# MiniGen.net
KiCad netlist of a schematic drawn in Altium Designer
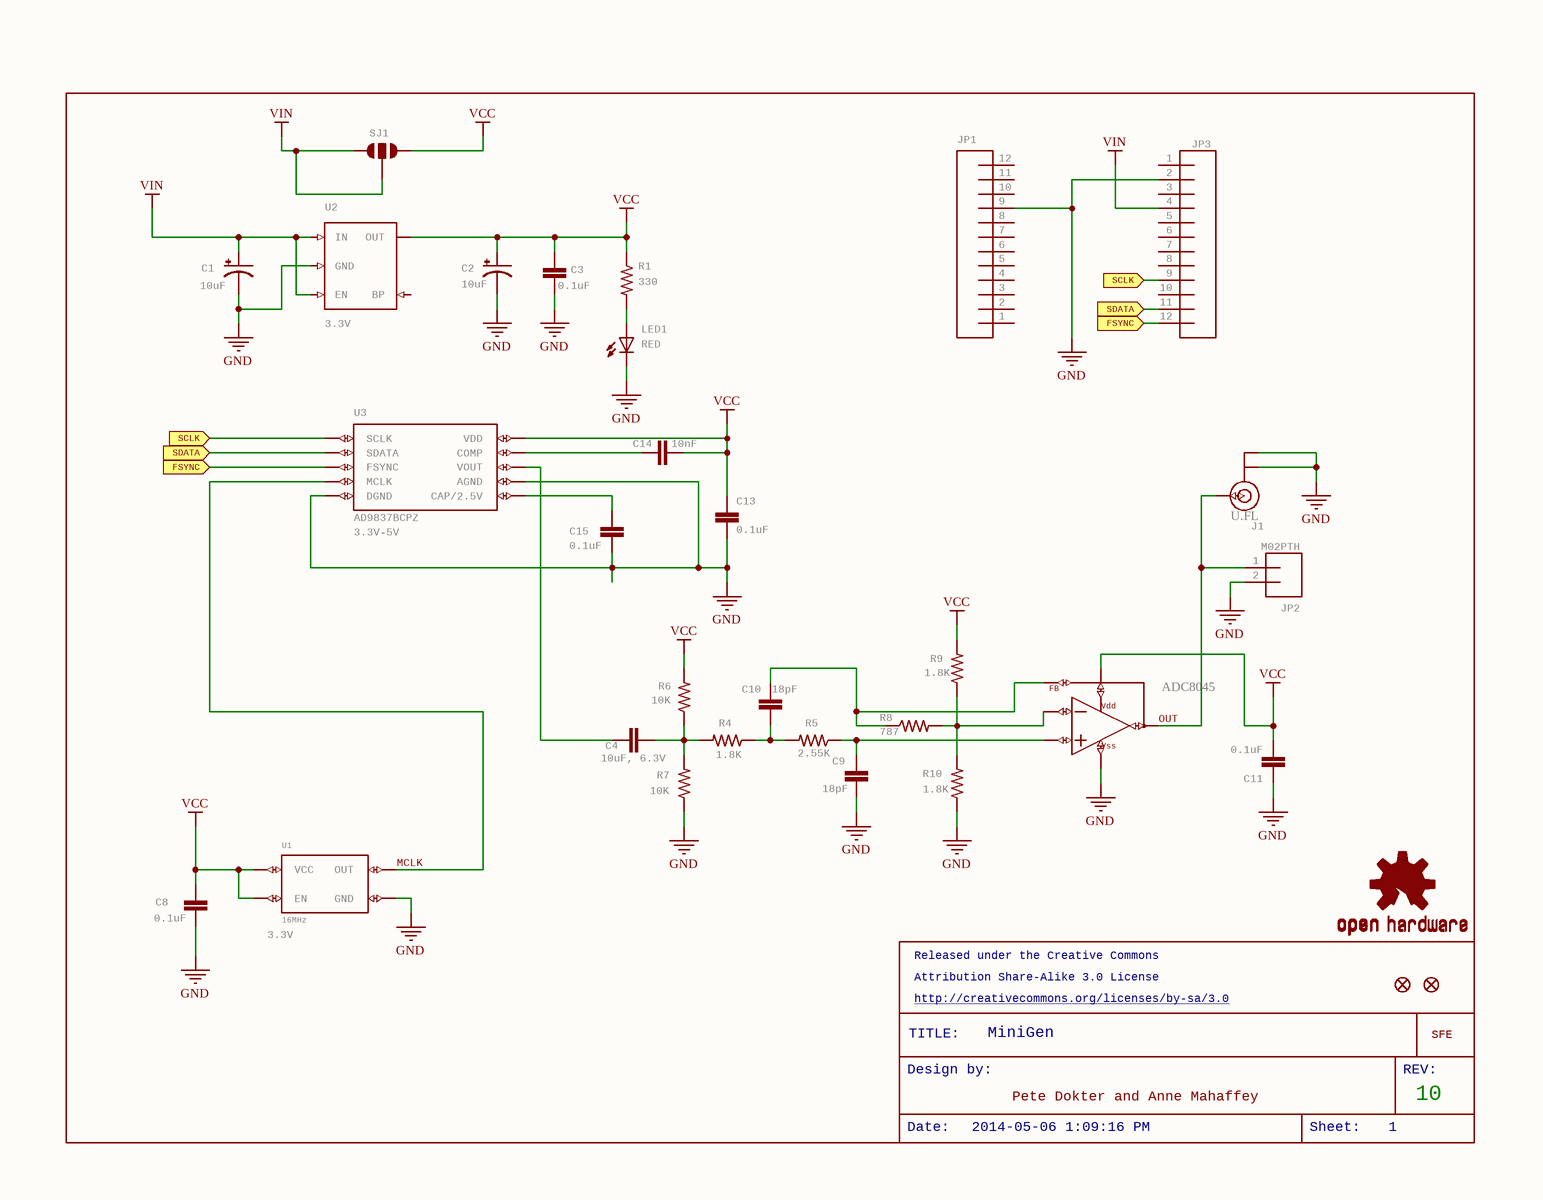
[diagram p0: MiniGen.SchDoc]

(export (version "E")
  (design (tool "Eeschema 10.0.6"))
  (components
    (comp (ref "C1")
      (value "10uF")
      (footprint "EIA3528")
      (description "CAP-08063")
      (libsource (lib "SparkFun-Capacitors") (part "10UF-20V-10%(TANT)"))
    )
    (comp (ref "C2")
      (value "10uF")
      (footprint "EIA3528")
      (description "CAP-08063")
      (libsource (lib "SparkFun-Capacitors") (part "10UF-20V-10%(TANT)"))
    )
    (comp (ref "C3")
      (value "0.1uF")
      (footprint "0603-CAP")
      (description "CAP-00810 Ceramic Standard decoupling cap")
      (libsource (lib "SparkFun-Capacitors") (part "0.1UF-25V(+80/-20%)(0603)"))
    )
    (comp (ref "C4")
      (value "10uF, 6.3V")
      (footprint "0603-CAP")
      (description "CAP-11015")
      (libsource (lib "SparkFun-Capacitors") (part "10UF-6.3V-20%(0603)"))
    )
    (comp (ref "C8")
      (value "0.1uF")
      (footprint "0603-CAP")
      (description "CAP-00810 Ceramic Standard decoupling cap")
      (libsource (lib "SparkFun-Capacitors") (part "0.1UF-25V(+80/-20%)(0603)"))
    )
    (comp (ref "C9")
      (value "18pF")
      (footprint "0603-CAP")
      (description "CAP-08267")
      (libsource (lib "SparkFun-Capacitors") (part "18PF-50V-5%(0603)"))
    )
    (comp (ref "C10")
      (value "18pF")
      (footprint "0603-CAP")
      (description "CAP-08267")
      (libsource (lib "SparkFun-Capacitors") (part "18PF-50V-5%(0603)"))
    )
    (comp (ref "C11")
      (value "0.1uF")
      (footprint "0603-CAP")
      (description "CAP-00810 Ceramic Standard decoupling cap")
      (libsource (lib "") (part "0.1UF-25V(+80/-20%)(0603)_1"))
    )
    (comp (ref "C13")
      (value "0.1uF")
      (footprint "0603-CAP")
      (description "CAP-00810 Ceramic Standard decoupling cap")
      (libsource (lib "SparkFun-Capacitors") (part "0.1UF-25V(+80/-20%)(0603)"))
    )
    (comp (ref "C14")
      (value "10nF")
      (footprint "0603-CAP")
      (description "CAP-00867")
      (libsource (lib "SparkFun-Capacitors") (part "10NF/10000PF-50V-10%(0603)"))
    )
    (comp (ref "C15")
      (value "0.1uF")
      (footprint "0603-CAP")
      (description "CAP-00810 Ceramic Standard decoupling cap")
      (libsource (lib "SparkFun-Capacitors") (part "0.1UF-25V(+80/-20%)(0603)"))
    )
    (comp (ref "FID1")
      (value "FIDUCIAL1X2")
      (footprint "FIDUCIAL-1X2")
      (description "Fiducial Alignment PointsVarious fiducial points for machine vision alignment.")
      (libsource (lib "SparkFun-Aesthetics") (part "FIDUCIAL1X2"))
    )
    (comp (ref "FID2")
      (value "FIDUCIAL1X2")
      (footprint "FIDUCIAL-1X2")
      (description "Fiducial Alignment PointsVarious fiducial points for machine vision alignment.")
      (libsource (lib "SparkFun-Aesthetics") (part "FIDUCIAL1X2"))
    )
    (comp (ref "J1")
      (value "U.FL")
      (footprint "U.FL")
      (description "SMD antenna connector- WRL-09144")
      (libsource (lib "SparkFun-Connectors") (part "U.FL"))
    )
    (comp (ref "JP1")
      (value "M12PTH")
      (footprint "1X12")
      (libsource (lib "SparkFun-Connectors") (part "M12PTH"))
    )
    (comp (ref "JP2")
      (value "M02PTH")
      (footprint "1X02")
      (libsource (lib "SparkFun-Connectors") (part "M02PTH"))
    )
    (comp (ref "JP3")
      (value "M12PTH")
      (footprint "1X12")
      (libsource (lib "SparkFun-Connectors") (part "M12PTH"))
    )
    (comp (ref "JP4")
      (value "LOGO-SFENEW")
      (footprint "SFE-NEW-WEBLOGO")
      (description "Spark Fun Electronics PCB LogoThis is the standard Spark Fun Electronics PCB logo.")
      (fields (field (name "SFE") "SFE"))
      (libsource (lib "SparkFun-Aesthetics") (part "LOGO-SFENEW"))
    )
    (comp (ref "LED1")
      (value "RED")
      (footprint "LED-0603")
      (description "Assorted Red LEDs LilyPad 1206- DIO-09912 1206- DIO-00809 0603- DIO-00819")
      (libsource (lib "SparkFun-LED") (part "LED-RED0603"))
    )
    (comp (ref "R1")
      (value "330")
      (footprint "0603-RES")
      (description "RES-00818")
      (libsource (lib "SparkFun-Resistors") (part "330OHM1/10W1%(0603)"))
    )
    (comp (ref "R4")
      (value "1.8K")
      (footprint "0603-RES")
      (description "RES-09119")
      (libsource (lib "SparkFun-Resistors") (part "1.8KOHM1/10W1%(0603)"))
    )
    (comp (ref "R5")
      (value "2.55K")
      (footprint "0603-RES")
      (description "RES-11227")
      (libsource (lib "SparkFun-Resistors") (part "2.55KOHM-1/10W-1%(0603)"))
    )
    (comp (ref "R6")
      (value "10K")
      (footprint "0603-RES")
      (description "RES-00824")
      (libsource (lib "SparkFun-Resistors") (part "10KOHM1/10W1%(0603)0603"))
    )
    (comp (ref "R7")
      (value "10K")
      (footprint "0603-RES")
      (description "RES-00824")
      (libsource (lib "SparkFun-Resistors") (part "10KOHM1/10W1%(0603)0603"))
    )
    (comp (ref "R8")
      (value "787")
      (footprint "0603-RES")
      (description "787-ohm SMT 1/10W - 1% (0603) RES-11228")
      (libsource (lib "SparkFun-Resistors") (part "787-1%"))
    )
    (comp (ref "R9")
      (value "1.8K")
      (footprint "0603-RES")
      (description "RES-09119")
      (libsource (lib "SparkFun-Resistors") (part "1.8KOHM1/10W1%(0603)"))
    )
    (comp (ref "R10")
      (value "1.8K")
      (footprint "0603-RES")
      (description "RES-09119")
      (libsource (lib "SparkFun-Resistors") (part "1.8KOHM1/10W1%(0603)"))
    )
    (comp (ref "SJ1")
      (value "SOLDERJUMPER_2WAYT")
      (footprint "SJ_2")
      (description "Solder Jumper2 way solder jumper")
      (libsource (lib "SparkFun-Passives") (part "SOLDERJUMPER_2WAYT"))
    )
    (comp (ref "U$2")
      (value "OSHW-LOGOS")
      (footprint "OSHW-LOGO-S")
      (libsource (lib "SparkFun-Aesthetics") (part "OSHW-LOGOS"))
    )
    (comp (ref "U1")
      (value "16MHz")
      (footprint "CRYSTAL-SMD-7X5")
      (description "Generic 5x3 and 7x5 oscillators")
      (fields (field (name "LIBRARYNAME") "SparkFun-FreqCtrl"))
      (libsource (lib "SparkFun-FreqCtrl") (part "OSCILLATORXTAL-11225"))
    )
    (comp (ref "U2")
      (value "3.3V")
      (footprint "SOT23-5")
      (description "MIC5205 150mA vreg 3.3V - VREG-00822 5V - VREG-00823")
      (libsource (lib "SparkFun-PowerIC") (part "MIC52053.3V"))
    )
    (comp (ref "U3")
      (value "AD9837BCPZ")
      (footprint "AD9837")
      (description "Programmable waveform generator, sine, triangular, and square wave outputs.")
      (libsource (lib "SparkFun-AnalogIC") (part "AD9837"))
    )
    (comp (ref "U4")
      (value "ADC8045")
      (footprint "SO08")
      (description "Unity-gain stable feedback amplifier. Low noise, low distortion, 1GHz BW.")
      (fields (field (name "VSS") "Vss") (field (name "VDD") "Vdd") (field (name "FB") "FB"))
      (libsource (lib "SparkFun-AnalogIC") (part "ADC8045"))
    )
  )
  (nets
    (net (code "1") (name "/FSYNC") (class "Default")
      (node (ref "JP3") (pin "12") (pinfunction "12_12") (pintype "passive"))
      (node (ref "U3") (pin "P$8") (pinfunction "FSYNC_P$8") (pintype "bidirectional"))
    )
    (net (code "2") (name "/MCLK") (class "Default")
      (node (ref "U1") (pin "P$3") (pinfunction "OUT_P$3") (pintype "bidirectional"))
      (node (ref "U3") (pin "P$5") (pinfunction "MCLK_P$5") (pintype "bidirectional"))
    )
    (net (code "3") (name "/OUT") (class "Default")
      (node (ref "J1") (pin "P$3") (pinfunction "SIGNAL_P$3") (pintype "bidirectional"))
      (node (ref "JP2") (pin "1") (pinfunction "1_1") (pintype "passive"))
      (node (ref "U4") (pin "6") (pinfunction "OUT_6") (pintype "bidirectional"))
    )
    (net (code "4") (name "/SCLK") (class "Default")
      (node (ref "JP3") (pin "9") (pinfunction "9_9") (pintype "passive"))
      (node (ref "U3") (pin "P$7") (pinfunction "SCLK_P$7") (pintype "bidirectional"))
    )
    (net (code "5") (name "/SDATA") (class "Default")
      (node (ref "JP3") (pin "11") (pinfunction "11_11") (pintype "passive"))
      (node (ref "U3") (pin "P$6") (pinfunction "SDATA_P$6") (pintype "bidirectional"))
    )
    (net (code "6") (name "GND") (class "Default")
      (node (ref "C1") (pin "C") (pinfunction "-_C") (pintype "passive"))
      (node (ref "C11") (pin "1") (pinfunction "1_1") (pintype "passive"))
      (node (ref "C13") (pin "2") (pinfunction "2_2") (pintype "passive"))
      (node (ref "C15") (pin "2") (pinfunction "2_2") (pintype "passive"))
      (node (ref "C2") (pin "C") (pinfunction "-_C") (pintype "passive"))
      (node (ref "C3") (pin "2") (pinfunction "2_2") (pintype "passive"))
      (node (ref "C8") (pin "2") (pinfunction "2_2") (pintype "passive"))
      (node (ref "C9") (pin "1") (pinfunction "1_1") (pintype "passive"))
      (node (ref "J1") (pin "P$1") (pinfunction "GND_P$1") (pintype "bidirectional"))
      (node (ref "J1") (pin "P$2") (pinfunction "GND_P$2") (pintype "bidirectional"))
      (node (ref "JP1") (pin "9") (pinfunction "9_9") (pintype "passive"))
      (node (ref "JP2") (pin "2") (pinfunction "2_2") (pintype "passive"))
      (node (ref "JP3") (pin "2") (pinfunction "2_2") (pintype "passive"))
      (node (ref "LED1") (pin "C") (pinfunction "C_C") (pintype "passive"))
      (node (ref "R10") (pin "1") (pinfunction "1_1") (pintype "passive"))
      (node (ref "R7") (pin "1") (pinfunction "1_1") (pintype "passive"))
      (node (ref "U1") (pin "P$2") (pinfunction "GND_P$2") (pintype "bidirectional"))
      (node (ref "U2") (pin "2") (pinfunction "GND_2") (pintype "input"))
      (node (ref "U3") (pin "P$0_P$4") (pinfunction "DGND_P$0_P$4") (pintype "bidirectional"))
      (node (ref "U3") (pin "P$9") (pinfunction "AGND_P$9") (pintype "bidirectional"))
      (node (ref "U4") (pin "4") (pinfunction "VSS_4") (pintype "bidirectional"))
    )
    (net (code "7") (name "Net-(C4-Pad2)") (class "Default")
      (node (ref "C4") (pin "2") (pinfunction "2_2") (pintype "passive"))
      (node (ref "R4") (pin "2") (pinfunction "2_2") (pintype "passive"))
      (node (ref "R6") (pin "1") (pinfunction "1_1") (pintype "passive"))
      (node (ref "R7") (pin "2") (pinfunction "2_2") (pintype "passive"))
    )
    (net (code "8") (name "Net-(C10-Pad1)") (class "Default")
      (node (ref "C10") (pin "1") (pinfunction "1_1") (pintype "passive"))
      (node (ref "R4") (pin "1") (pinfunction "1_1") (pintype "passive"))
      (node (ref "R5") (pin "2") (pinfunction "2_2") (pintype "passive"))
    )
    (net (code "9") (name "Net-(LED1-PadA)") (class "Default")
      (node (ref "LED1") (pin "A") (pinfunction "A_A") (pintype "passive"))
      (node (ref "R1") (pin "2") (pinfunction "2_2") (pintype "passive"))
    )
    (net (code "10") (name "Net-(U3-CAP{slash}2.5V)") (class "Default")
      (node (ref "C15") (pin "1") (pinfunction "1_1") (pintype "passive"))
      (node (ref "U3") (pin "P$3") (pinfunction "CAP/2.5V_P$3") (pintype "bidirectional"))
    )
    (net (code "11") (name "Net-(U3-COMP)") (class "Default")
      (node (ref "C14") (pin "1") (pinfunction "1_1") (pintype "passive"))
      (node (ref "U3") (pin "P$1") (pinfunction "COMP_P$1") (pintype "bidirectional"))
    )
    (net (code "12") (name "Net-(U3-VOUT)") (class "Default")
      (node (ref "C4") (pin "1") (pinfunction "1_1") (pintype "passive"))
      (node (ref "U3") (pin "P$10") (pinfunction "VOUT_P$10") (pintype "bidirectional"))
    )
    (net (code "13") (name "Net-(U4-FB)") (class "Default")
      (node (ref "C10") (pin "2") (pinfunction "2_2") (pintype "passive"))
      (node (ref "R8") (pin "1") (pinfunction "1_1") (pintype "passive"))
      (node (ref "U4") (pin "1") (pinfunction "FB_1") (pintype "bidirectional"))
    )
    (net (code "14") (name "Net-(U4-IN+)") (class "Default")
      (node (ref "C9") (pin "2") (pinfunction "2_2") (pintype "passive"))
      (node (ref "R5") (pin "1") (pinfunction "1_1") (pintype "passive"))
      (node (ref "U4") (pin "3") (pinfunction "IN+_3") (pintype "bidirectional"))
    )
    (net (code "15") (name "Net-(U4-IN-)") (class "Default")
      (node (ref "R10") (pin "2") (pinfunction "2_2") (pintype "passive"))
      (node (ref "R8") (pin "2") (pinfunction "2_2") (pintype "passive"))
      (node (ref "R9") (pin "1") (pinfunction "1_1") (pintype "passive"))
      (node (ref "U4") (pin "2") (pinfunction "IN-_2") (pintype "bidirectional"))
    )
    (net (code "16") (name "VCC") (class "Default")
      (node (ref "C11") (pin "2") (pinfunction "2_2") (pintype "passive"))
      (node (ref "C13") (pin "1") (pinfunction "1_1") (pintype "passive"))
      (node (ref "C14") (pin "2") (pinfunction "2_2") (pintype "passive"))
      (node (ref "C2") (pin "A") (pinfunction "+_A") (pintype "passive"))
      (node (ref "C3") (pin "1") (pinfunction "1_1") (pintype "passive"))
      (node (ref "C8") (pin "1") (pinfunction "1_1") (pintype "passive"))
      (node (ref "R1") (pin "1") (pinfunction "1_1") (pintype "passive"))
      (node (ref "R6") (pin "2") (pinfunction "2_2") (pintype "passive"))
      (node (ref "R9") (pin "2") (pinfunction "2_2") (pintype "passive"))
      (node (ref "SJ1") (pin "3") (pinfunction "3_3") (pintype "passive"))
      (node (ref "U1") (pin "P$1") (pinfunction "EN_P$1") (pintype "bidirectional"))
      (node (ref "U1") (pin "P$4") (pinfunction "VCC_P$4") (pintype "bidirectional"))
      (node (ref "U2") (pin "5") (pinfunction "OUT_5") (pintype "passive"))
      (node (ref "U3") (pin "P$2") (pinfunction "VDD_P$2") (pintype "bidirectional"))
      (node (ref "U4") (pin "7") (pinfunction "VDD_7") (pintype "bidirectional"))
    )
    (net (code "17") (name "VIN") (class "Default")
      (node (ref "C1") (pin "A") (pinfunction "+_A") (pintype "passive"))
      (node (ref "JP3") (pin "4") (pinfunction "4_4") (pintype "passive"))
      (node (ref "SJ1") (pin "1") (pinfunction "1_1") (pintype "passive"))
      (node (ref "SJ1") (pin "2") (pinfunction "2_2") (pintype "passive"))
      (node (ref "U2") (pin "1") (pinfunction "IN_1") (pintype "input"))
      (node (ref "U2") (pin "3") (pinfunction "EN_3") (pintype "input"))
    )
    (net (code "18") (name "unconnected-(JP1-Pad1)") (class "Default")
      (node (ref "JP1") (pin "1") (pinfunction "1_1") (pintype "passive"))
    )
    (net (code "19") (name "unconnected-(JP1-Pad2)") (class "Default")
      (node (ref "JP1") (pin "2") (pinfunction "2_2") (pintype "passive"))
    )
    (net (code "20") (name "unconnected-(JP1-Pad3)") (class "Default")
      (node (ref "JP1") (pin "3") (pinfunction "3_3") (pintype "passive"))
    )
    (net (code "21") (name "unconnected-(JP1-Pad4)") (class "Default")
      (node (ref "JP1") (pin "4") (pinfunction "4_4") (pintype "passive"))
    )
    (net (code "22") (name "unconnected-(JP1-Pad5)") (class "Default")
      (node (ref "JP1") (pin "5") (pinfunction "5_5") (pintype "passive"))
    )
    (net (code "23") (name "unconnected-(JP1-Pad6)") (class "Default")
      (node (ref "JP1") (pin "6") (pinfunction "6_6") (pintype "passive"))
    )
    (net (code "24") (name "unconnected-(JP1-Pad7)") (class "Default")
      (node (ref "JP1") (pin "7") (pinfunction "7_7") (pintype "passive"))
    )
    (net (code "25") (name "unconnected-(JP1-Pad8)") (class "Default")
      (node (ref "JP1") (pin "8") (pinfunction "8_8") (pintype "passive"))
    )
    (net (code "26") (name "unconnected-(JP1-Pad10)") (class "Default")
      (node (ref "JP1") (pin "10") (pinfunction "10_10") (pintype "passive"))
    )
    (net (code "27") (name "unconnected-(JP1-Pad11)") (class "Default")
      (node (ref "JP1") (pin "11") (pinfunction "11_11") (pintype "passive"))
    )
    (net (code "28") (name "unconnected-(JP1-Pad12)") (class "Default")
      (node (ref "JP1") (pin "12") (pinfunction "12_12") (pintype "passive"))
    )
    (net (code "29") (name "unconnected-(JP3-Pad1)") (class "Default")
      (node (ref "JP3") (pin "1") (pinfunction "1_1") (pintype "passive"))
    )
    (net (code "30") (name "unconnected-(JP3-Pad3)") (class "Default")
      (node (ref "JP3") (pin "3") (pinfunction "3_3") (pintype "passive"))
    )
    (net (code "31") (name "unconnected-(JP3-Pad5)") (class "Default")
      (node (ref "JP3") (pin "5") (pinfunction "5_5") (pintype "passive"))
    )
    (net (code "32") (name "unconnected-(JP3-Pad6)") (class "Default")
      (node (ref "JP3") (pin "6") (pinfunction "6_6") (pintype "passive"))
    )
    (net (code "33") (name "unconnected-(JP3-Pad7)") (class "Default")
      (node (ref "JP3") (pin "7") (pinfunction "7_7") (pintype "passive"))
    )
    (net (code "34") (name "unconnected-(JP3-Pad8)") (class "Default")
      (node (ref "JP3") (pin "8") (pinfunction "8_8") (pintype "passive"))
    )
    (net (code "35") (name "unconnected-(JP3-Pad10)") (class "Default")
      (node (ref "JP3") (pin "10") (pinfunction "10_10") (pintype "passive"))
    )
    (net (code "36") (name "unconnected-(U2-BP-Pad4)") (class "Default")
      (node (ref "U2") (pin "4") (pinfunction "BP_4") (pintype "input"))
    )
  )
)
